# dac_connector_board.net
KiCad netlist of a schematic drawn in EAGLE
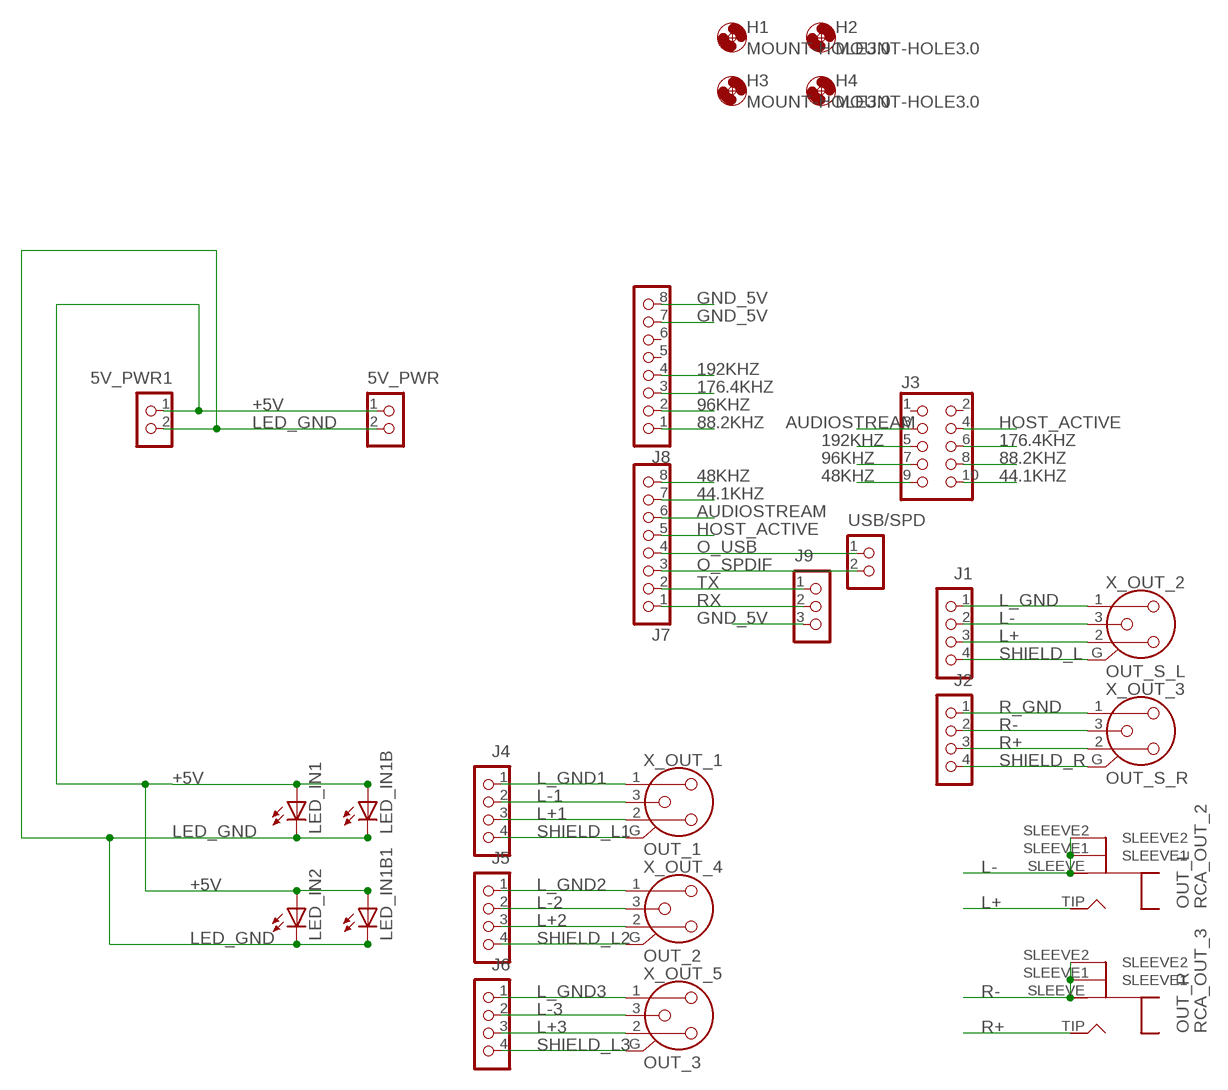
[diagram p0: schematic, sheet 1]

(export (version "E")
  (design (tool "Eeschema 10.0.6"))
  (components
    (comp (ref "5V_PWR")
      (value "5V PWR")
      (footprint "eagle-import:M1X2")
      (libsource (lib "eagle-import") (part "CON_HEADER_1X02-PTH"))
    )
    (comp (ref "5V_PWR1")
      (value "5V PWR")
      (footprint "eagle-import:M1X2")
      (libsource (lib "eagle-import") (part "CON_HEADER_1X02-PTH"))
    )
    (comp (ref "H1")
      (value "MOUNT-HOLE3.0")
      (footprint "eagle-import:3,0")
      (libsource (lib "eagle-import") (part "MOUNT-HOLE3.0"))
    )
    (comp (ref "H2")
      (value "MOUNT-HOLE3.0")
      (footprint "eagle-import:3,0")
      (libsource (lib "eagle-import") (part "MOUNT-HOLE3.0"))
    )
    (comp (ref "H3")
      (value "MOUNT-HOLE3.0")
      (footprint "eagle-import:3,0")
      (libsource (lib "eagle-import") (part "MOUNT-HOLE3.0"))
    )
    (comp (ref "H4")
      (value "MOUNT-HOLE3.0")
      (footprint "eagle-import:3,0")
      (libsource (lib "eagle-import") (part "MOUNT-HOLE3.0"))
    )
    (comp (ref "J1")
      (value "CON_HEADER_1X04")
      (footprint "eagle-import:M1X4")
      (libsource (lib "eagle-import") (part "CON_HEADER_1X04"))
    )
    (comp (ref "J2")
      (value "CON_HEADER_1X04")
      (footprint "eagle-import:M1X4")
      (libsource (lib "eagle-import") (part "CON_HEADER_1X04"))
    )
    (comp (ref "J3")
      (value "DAC")
      (footprint "eagle-import:M2X5")
      (libsource (lib "eagle-import") (part "CON_HEADER_2X05-PTH"))
    )
    (comp (ref "J4")
      (value "CON_OUT_1")
      (footprint "eagle-import:M1X4")
      (libsource (lib "eagle-import") (part "CON_HEADER_1X04"))
    )
    (comp (ref "J5")
      (value "CON_OUT_2")
      (footprint "eagle-import:M1X4")
      (libsource (lib "eagle-import") (part "CON_HEADER_1X04"))
    )
    (comp (ref "J6")
      (value "CON_OUT_3")
      (footprint "eagle-import:M1X4")
      (libsource (lib "eagle-import") (part "CON_HEADER_1X04"))
    )
    (comp (ref "J7")
      (value "ARD1")
      (footprint "eagle-import:M1X8")
      (libsource (lib "eagle-import") (part "CON_HEADER_1X08-PTH"))
    )
    (comp (ref "J8")
      (value "ARD2")
      (footprint "eagle-import:M1X8")
      (libsource (lib "eagle-import") (part "CON_HEADER_1X08-PTH"))
    )
    (comp (ref "J9")
      (value "SERIAL")
      (footprint "eagle-import:M1X3")
      (libsource (lib "eagle-import") (part "CON_HEADER_1X03-PTH"))
    )
    (comp (ref "LED_IN1")
      (value "TLLG4400")
      (footprint "eagle-import:LED3MM")
      (fields (field (name "MF") "VISHAY SEMICONDUCTOR"))
      (libsource (lib "eagle-import") (part "TLLG4400"))
    )
    (comp (ref "LED_IN1B")
      (value "TLLG4400")
      (footprint "eagle-import:LED3MM")
      (fields
        (field (name "MF") "VISHAY SEMICONDUCTOR")
        (field (name "MF_1") "VISHAY SEMICONDUCTOR")
        (field (name "OC_FARNELL") "1612435")
      )
      (libsource (lib "eagle-import") (part "TLLG4400"))
    )
    (comp (ref "LED_IN1B1")
      (value "TLLG4400")
      (footprint "eagle-import:LED3MM")
      (fields
        (field (name "MF") "VISHAY SEMICONDUCTOR")
        (field (name "MF_1") "VISHAY SEMICONDUCTOR")
        (field (name "OC_FARNELL") "1612435")
      )
      (libsource (lib "eagle-import") (part "TLLG4400"))
    )
    (comp (ref "LED_IN2")
      (value "TLLG4400")
      (footprint "eagle-import:LED3MM")
      (fields (field (name "MF") "VISHAY SEMICONDUCTOR"))
      (libsource (lib "eagle-import") (part "TLLG4400"))
    )
    (comp (ref "RCA_OUT_2")
      (value "OUT_L")
      (footprint "eagle-import:MONO_JACK")
      (libsource (lib "eagle-import") (part "MONO_JACKGAEL"))
    )
    (comp (ref "RCA_OUT_3")
      (value "OUT_R")
      (footprint "eagle-import:MONO_JACK")
      (libsource (lib "eagle-import") (part "MONO_JACKGAEL"))
    )
    (comp (ref "USB/SPD")
      (value "IN_SEL")
      (footprint "eagle-import:M1X2")
      (libsource (lib "eagle-import") (part "CON_HEADER_1X02-PTH"))
    )
    (comp (ref "X_OUT_1")
      (value "OUT_1")
      (footprint "eagle-import:NC3MBH")
      (fields
        (field (name "MF") "NEUTRIK")
        (field (name "MPN") "NC3MBH")
        (field (name "MF_1") "NEUTRIK")
        (field (name "MPN_1") "NC3MBH")
        (field (name "OC_FARNELL") "unknown")
        (field (name "OC_NEWARK") "91F3470")
      )
      (libsource (lib "eagle-import") (part "NC3MBH"))
    )
    (comp (ref "X_OUT_2")
      (value "OUT_S_L")
      (footprint "eagle-import:NC3MBH")
      (fields
        (field (name "MF") "NEUTRIK")
        (field (name "MPN") "NC3MBH")
        (field (name "MF_1") "NEUTRIK")
        (field (name "MPN_1") "NC3MBH")
        (field (name "OC_FARNELL") "unknown")
        (field (name "OC_NEWARK") "91F3470")
      )
      (libsource (lib "eagle-import") (part "NC3MBH"))
    )
    (comp (ref "X_OUT_3")
      (value "OUT_S_R")
      (footprint "eagle-import:NC3MBH")
      (fields
        (field (name "MF") "NEUTRIK")
        (field (name "MPN") "NC3MBH")
        (field (name "MF_1") "NEUTRIK")
        (field (name "MPN_1") "NC3MBH")
        (field (name "OC_FARNELL") "unknown")
        (field (name "OC_NEWARK") "91F3470")
      )
      (libsource (lib "eagle-import") (part "NC3MBH"))
    )
    (comp (ref "X_OUT_4")
      (value "OUT_2")
      (footprint "eagle-import:NC3MBH")
      (fields
        (field (name "MF") "NEUTRIK")
        (field (name "MPN") "NC3MBH")
        (field (name "MF_1") "NEUTRIK")
        (field (name "MPN_1") "NC3MBH")
        (field (name "OC_FARNELL") "unknown")
        (field (name "OC_NEWARK") "91F3470")
      )
      (libsource (lib "eagle-import") (part "NC3MBH"))
    )
    (comp (ref "X_OUT_5")
      (value "OUT_3")
      (footprint "eagle-import:NC3MBH")
      (fields
        (field (name "MF") "NEUTRIK")
        (field (name "MPN") "NC3MBH")
        (field (name "MF_1") "NEUTRIK")
        (field (name "MPN_1") "NC3MBH")
        (field (name "OC_FARNELL") "unknown")
        (field (name "OC_NEWARK") "91F3470")
      )
      (libsource (lib "eagle-import") (part "NC3MBH"))
    )
  )
  (nets
    (net (code "1") (name "/+5V") (class "Default")
      (node (ref "5V_PWR") (pin "1") (pinfunction "1_1") (pintype "passive"))
      (node (ref "5V_PWR1") (pin "1") (pinfunction "1_1") (pintype "passive"))
      (node (ref "LED_IN1") (pin "A") (pinfunction "A_A") (pintype "passive"))
      (node (ref "LED_IN1B") (pin "A") (pinfunction "A_A") (pintype "passive"))
      (node (ref "LED_IN1B1") (pin "A") (pinfunction "A_A") (pintype "passive"))
      (node (ref "LED_IN2") (pin "A") (pinfunction "A_A") (pintype "passive"))
    )
    (net (code "2") (name "/44.1KHZ") (class "Default")
      (node (ref "J3") (pin "10") (pinfunction "10_10") (pintype "passive"))
      (node (ref "J7") (pin "7") (pinfunction "7_7") (pintype "passive"))
    )
    (net (code "3") (name "/48KHZ") (class "Default")
      (node (ref "J3") (pin "9") (pinfunction "9_9") (pintype "passive"))
      (node (ref "J7") (pin "8") (pinfunction "8_8") (pintype "passive"))
    )
    (net (code "4") (name "/88.2KHZ") (class "Default")
      (node (ref "J3") (pin "8") (pinfunction "8_8") (pintype "passive"))
      (node (ref "J8") (pin "1") (pinfunction "1_1") (pintype "passive"))
    )
    (net (code "5") (name "/96KHZ") (class "Default")
      (node (ref "J3") (pin "7") (pinfunction "7_7") (pintype "passive"))
      (node (ref "J8") (pin "2") (pinfunction "2_2") (pintype "passive"))
    )
    (net (code "6") (name "/176.4KHZ") (class "Default")
      (node (ref "J3") (pin "6") (pinfunction "6_6") (pintype "passive"))
      (node (ref "J8") (pin "3") (pinfunction "3_3") (pintype "passive"))
    )
    (net (code "7") (name "/192KHZ") (class "Default")
      (node (ref "J3") (pin "5") (pinfunction "5_5") (pintype "passive"))
      (node (ref "J8") (pin "4") (pinfunction "4_4") (pintype "passive"))
    )
    (net (code "8") (name "/AUDIOSTREAM") (class "Default")
      (node (ref "J3") (pin "3") (pinfunction "3_3") (pintype "passive"))
      (node (ref "J7") (pin "6") (pinfunction "6_6") (pintype "passive"))
    )
    (net (code "9") (name "/GND_5V") (class "Default")
      (node (ref "J8") (pin "7") (pinfunction "7_7") (pintype "passive"))
      (node (ref "J8") (pin "8") (pinfunction "8_8") (pintype "passive"))
      (node (ref "J9") (pin "3") (pinfunction "3_3") (pintype "bidirectional"))
    )
    (net (code "10") (name "/HOST_ACTIVE") (class "Default")
      (node (ref "J3") (pin "4") (pinfunction "4_4") (pintype "passive"))
      (node (ref "J7") (pin "5") (pinfunction "5_5") (pintype "passive"))
    )
    (net (code "11") (name "/L+") (class "Default")
      (node (ref "J1") (pin "3") (pinfunction "3_3") (pintype "bidirectional"))
      (node (ref "RCA_OUT_2") (pin "TIP") (pinfunction "TIP_TIP") (pintype "passive"))
      (node (ref "X_OUT_2") (pin "2") (pinfunction "2_2") (pintype "passive"))
    )
    (net (code "12") (name "/L+1") (class "Default")
      (node (ref "J4") (pin "3") (pinfunction "3_3") (pintype "bidirectional"))
      (node (ref "X_OUT_1") (pin "2") (pinfunction "2_2") (pintype "passive"))
    )
    (net (code "13") (name "/L+2") (class "Default")
      (node (ref "J5") (pin "3") (pinfunction "3_3") (pintype "bidirectional"))
      (node (ref "X_OUT_4") (pin "2") (pinfunction "2_2") (pintype "passive"))
    )
    (net (code "14") (name "/L+3") (class "Default")
      (node (ref "J6") (pin "3") (pinfunction "3_3") (pintype "bidirectional"))
      (node (ref "X_OUT_5") (pin "2") (pinfunction "2_2") (pintype "passive"))
    )
    (net (code "15") (name "/L-") (class "Default")
      (node (ref "J1") (pin "2") (pinfunction "2_2") (pintype "bidirectional"))
      (node (ref "RCA_OUT_2") (pin "SLEEVE") (pinfunction "SLEEVE_SLEEVE") (pintype "passive"))
      (node (ref "RCA_OUT_2") (pin "SLEEVE1") (pinfunction "SLEEVE1_SLEEVE1") (pintype "passive"))
      (node (ref "RCA_OUT_2") (pin "SLEEVE2") (pinfunction "SLEEVE2_SLEEVE2") (pintype "passive"))
      (node (ref "X_OUT_2") (pin "3") (pinfunction "3_3") (pintype "passive"))
    )
    (net (code "16") (name "/L-1") (class "Default")
      (node (ref "J4") (pin "2") (pinfunction "2_2") (pintype "bidirectional"))
      (node (ref "X_OUT_1") (pin "3") (pinfunction "3_3") (pintype "passive"))
    )
    (net (code "17") (name "/L-2") (class "Default")
      (node (ref "J5") (pin "2") (pinfunction "2_2") (pintype "bidirectional"))
      (node (ref "X_OUT_4") (pin "3") (pinfunction "3_3") (pintype "passive"))
    )
    (net (code "18") (name "/L-3") (class "Default")
      (node (ref "J6") (pin "2") (pinfunction "2_2") (pintype "bidirectional"))
      (node (ref "X_OUT_5") (pin "3") (pinfunction "3_3") (pintype "passive"))
    )
    (net (code "19") (name "/LED_GND") (class "Default")
      (node (ref "5V_PWR") (pin "2") (pinfunction "2_2") (pintype "passive"))
      (node (ref "5V_PWR1") (pin "2") (pinfunction "2_2") (pintype "passive"))
      (node (ref "LED_IN1") (pin "K") (pinfunction "C_K") (pintype "passive"))
      (node (ref "LED_IN1B") (pin "K") (pinfunction "C_K") (pintype "passive"))
      (node (ref "LED_IN1B1") (pin "K") (pinfunction "C_K") (pintype "passive"))
      (node (ref "LED_IN2") (pin "K") (pinfunction "C_K") (pintype "passive"))
    )
    (net (code "20") (name "/L_GND") (class "Default")
      (node (ref "J1") (pin "1") (pinfunction "1_1") (pintype "bidirectional"))
      (node (ref "X_OUT_2") (pin "1") (pinfunction "1_1") (pintype "passive"))
    )
    (net (code "21") (name "/L_GND1") (class "Default")
      (node (ref "J4") (pin "1") (pinfunction "1_1") (pintype "bidirectional"))
      (node (ref "X_OUT_1") (pin "1") (pinfunction "1_1") (pintype "passive"))
    )
    (net (code "22") (name "/L_GND2") (class "Default")
      (node (ref "J5") (pin "1") (pinfunction "1_1") (pintype "bidirectional"))
      (node (ref "X_OUT_4") (pin "1") (pinfunction "1_1") (pintype "passive"))
    )
    (net (code "23") (name "/L_GND3") (class "Default")
      (node (ref "J6") (pin "1") (pinfunction "1_1") (pintype "bidirectional"))
      (node (ref "X_OUT_5") (pin "1") (pinfunction "1_1") (pintype "passive"))
    )
    (net (code "24") (name "/O_SPDIF") (class "Default")
      (node (ref "J7") (pin "3") (pinfunction "3_3") (pintype "passive"))
      (node (ref "USB/SPD") (pin "2") (pinfunction "2_2") (pintype "passive"))
    )
    (net (code "25") (name "/O_USB") (class "Default")
      (node (ref "J7") (pin "4") (pinfunction "4_4") (pintype "passive"))
      (node (ref "USB/SPD") (pin "1") (pinfunction "1_1") (pintype "passive"))
    )
    (net (code "26") (name "/R+") (class "Default")
      (node (ref "J2") (pin "3") (pinfunction "3_3") (pintype "bidirectional"))
      (node (ref "RCA_OUT_3") (pin "TIP") (pinfunction "TIP_TIP") (pintype "passive"))
      (node (ref "X_OUT_3") (pin "2") (pinfunction "2_2") (pintype "passive"))
    )
    (net (code "27") (name "/R-") (class "Default")
      (node (ref "J2") (pin "2") (pinfunction "2_2") (pintype "bidirectional"))
      (node (ref "RCA_OUT_3") (pin "SLEEVE") (pinfunction "SLEEVE_SLEEVE") (pintype "passive"))
      (node (ref "RCA_OUT_3") (pin "SLEEVE1") (pinfunction "SLEEVE1_SLEEVE1") (pintype "passive"))
      (node (ref "RCA_OUT_3") (pin "SLEEVE2") (pinfunction "SLEEVE2_SLEEVE2") (pintype "passive"))
      (node (ref "X_OUT_3") (pin "3") (pinfunction "3_3") (pintype "passive"))
    )
    (net (code "28") (name "/RX") (class "Default")
      (node (ref "J7") (pin "1") (pinfunction "1_1") (pintype "passive"))
      (node (ref "J9") (pin "2") (pinfunction "2_2") (pintype "bidirectional"))
    )
    (net (code "29") (name "/R_GND") (class "Default")
      (node (ref "J2") (pin "1") (pinfunction "1_1") (pintype "bidirectional"))
      (node (ref "X_OUT_3") (pin "1") (pinfunction "1_1") (pintype "passive"))
    )
    (net (code "30") (name "/SHIELD_L") (class "Default")
      (node (ref "J1") (pin "4") (pinfunction "4_4") (pintype "bidirectional"))
      (node (ref "X_OUT_2") (pin "G") (pinfunction "G_G") (pintype "passive"))
    )
    (net (code "31") (name "/SHIELD_L1") (class "Default")
      (node (ref "J4") (pin "4") (pinfunction "4_4") (pintype "bidirectional"))
      (node (ref "X_OUT_1") (pin "G") (pinfunction "G_G") (pintype "passive"))
    )
    (net (code "32") (name "/SHIELD_L2") (class "Default")
      (node (ref "J5") (pin "4") (pinfunction "4_4") (pintype "bidirectional"))
      (node (ref "X_OUT_4") (pin "G") (pinfunction "G_G") (pintype "passive"))
    )
    (net (code "33") (name "/SHIELD_L3") (class "Default")
      (node (ref "J6") (pin "4") (pinfunction "4_4") (pintype "bidirectional"))
      (node (ref "X_OUT_5") (pin "G") (pinfunction "G_G") (pintype "passive"))
    )
    (net (code "34") (name "/SHIELD_R") (class "Default")
      (node (ref "J2") (pin "4") (pinfunction "4_4") (pintype "bidirectional"))
      (node (ref "X_OUT_3") (pin "G") (pinfunction "G_G") (pintype "passive"))
    )
    (net (code "35") (name "/TX") (class "Default")
      (node (ref "J7") (pin "2") (pinfunction "2_2") (pintype "passive"))
      (node (ref "J9") (pin "1") (pinfunction "1_1") (pintype "bidirectional"))
    )
    (net (code "36") (name "unconnected-(J3-Pad1)") (class "Default")
      (node (ref "J3") (pin "1") (pinfunction "1_1") (pintype "passive"))
    )
    (net (code "37") (name "unconnected-(J3-Pad2)") (class "Default")
      (node (ref "J3") (pin "2") (pinfunction "2_2") (pintype "passive"))
    )
    (net (code "38") (name "unconnected-(J8-Pad5)") (class "Default")
      (node (ref "J8") (pin "5") (pinfunction "5_5") (pintype "passive"))
    )
    (net (code "39") (name "unconnected-(J8-Pad6)") (class "Default")
      (node (ref "J8") (pin "6") (pinfunction "6_6") (pintype "passive"))
    )
  )
)
